# stepper_driver.net
KiCad netlist of a schematic drawn in Altium Designer
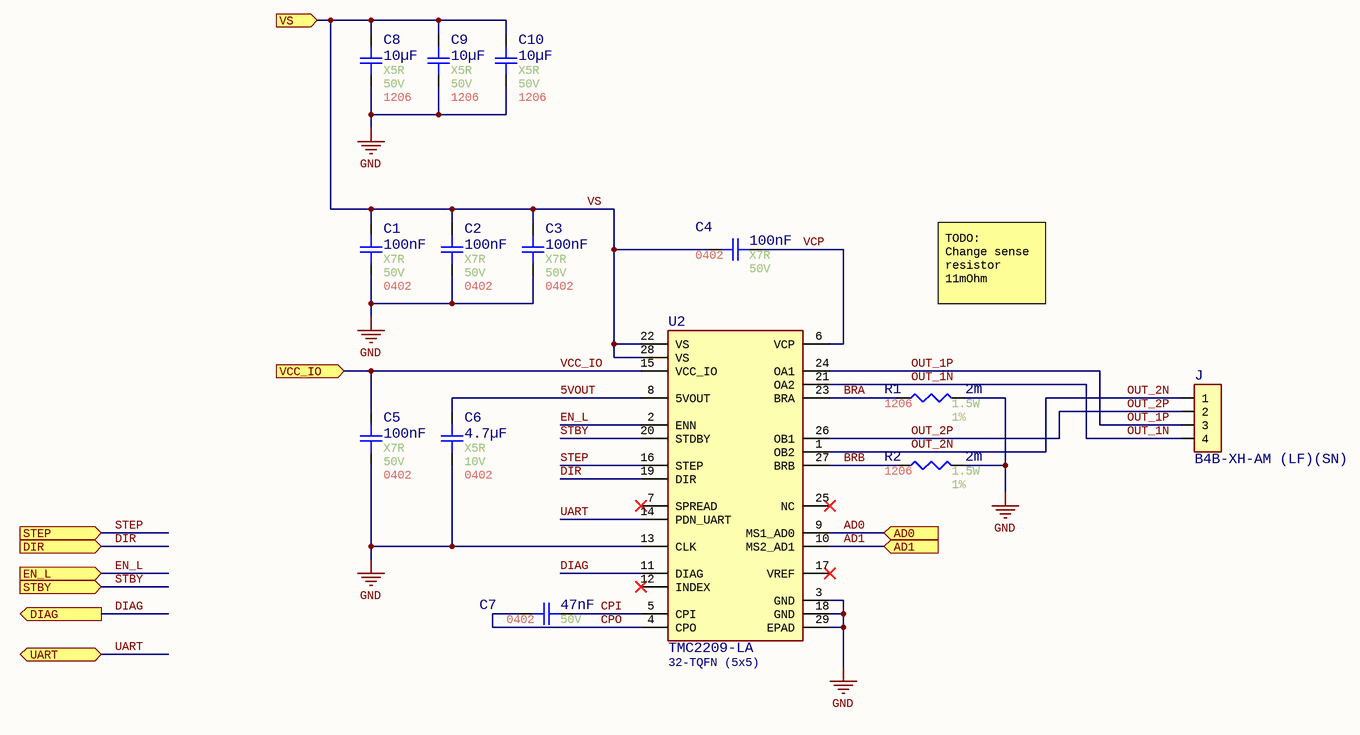
[diagram p0: stepper_driver.SchDoc]

(export (version "E")
  (design (tool "Eeschema 10.0.6"))
  (components
    (comp (ref "C1")
      (value "100nF")
      (footprint "Generic 0402 capacitor")
      (fields
        (field (name "TEMPERATURE COEFFICIENT") "X7R")
        (field (name "VOLTAGE RATING") "50V")
        (field (name "CASE/PACKAGE") "0402")
        (field (name "TOLERANCE") "10%")
        (field (name "Comment") "GRT155R71H104KE01D")
      )
      (libsource (lib "Raise Robotics") (part "Unpolarized Capacitor"))
    )
    (comp (ref "C2")
      (value "100nF")
      (footprint "Generic 0402 capacitor")
      (fields
        (field (name "TEMPERATURE COEFFICIENT") "X7R")
        (field (name "VOLTAGE RATING") "50V")
        (field (name "CASE/PACKAGE") "0402")
        (field (name "TOLERANCE") "10%")
        (field (name "Comment") "GRT155R71H104KE01D")
      )
      (libsource (lib "Raise Robotics") (part "Unpolarized Capacitor"))
    )
    (comp (ref "C3")
      (value "100nF")
      (footprint "Generic 0402 capacitor")
      (fields
        (field (name "TEMPERATURE COEFFICIENT") "X7R")
        (field (name "VOLTAGE RATING") "50V")
        (field (name "CASE/PACKAGE") "0402")
        (field (name "TOLERANCE") "10%")
        (field (name "Comment") "GRT155R71H104KE01D")
      )
      (libsource (lib "Raise Robotics") (part "Unpolarized Capacitor"))
    )
    (comp (ref "C4")
      (value "100nF")
      (footprint "Generic 0402 capacitor")
      (fields
        (field (name "TEMPERATURE COEFFICIENT") "X7R")
        (field (name "VOLTAGE RATING") "50V")
        (field (name "CASE/PACKAGE") "0402")
        (field (name "TOLERANCE") "10%")
        (field (name "Comment") "GRT155R71H104KE01D")
      )
      (libsource (lib "Raise Robotics") (part "Unpolarized Capacitor"))
    )
    (comp (ref "C5")
      (value "100nF")
      (footprint "Generic 0402 capacitor")
      (fields
        (field (name "TEMPERATURE COEFFICIENT") "X7R")
        (field (name "VOLTAGE RATING") "50V")
        (field (name "CASE/PACKAGE") "0402")
        (field (name "TOLERANCE") "10%")
        (field (name "Comment") "GRT155R71H104KE01D")
      )
      (libsource (lib "Raise Robotics") (part "Unpolarized Capacitor"))
    )
    (comp (ref "C6")
      (value "4.7µF")
      (footprint "Generic 0402 capacitor")
      (fields
        (field (name "TEMPERATURE COEFFICIENT") "X5R")
        (field (name "VOLTAGE RATING") "10V")
        (field (name "CASE/PACKAGE") "0402")
        (field (name "TOLERANCE") "0%")
        (field (name "Comment") "GRT155R61A475ME13D")
      )
      (libsource (lib "Raise Robotics") (part "Unpolarized Capacitor"))
    )
    (comp (ref "C7")
      (value "47nF")
      (footprint "Generic 0402 capacitor")
      (description "50V 47nF X7R ±10% 0402 Multilayer Ceramic Capacitors MLCC - SMD/SMT ROHS")
      (fields
        (field (name "VOLTAGE RATING") "50V")
        (field (name "CASE/PACKAGE") "0402")
        (field (name "TOLERANCE") "10%")
        (field (name "Comment") "GRM155R71H473KE14D")
      )
      (libsource (lib "Raise Robotics") (part "Unpolarized Capacitor"))
    )
    (comp (ref "C8")
      (value "10µF")
      (footprint "Generic 1206 Capacitor")
      (fields
        (field (name "TEMPERATURE COEFFICIENT") "X5R")
        (field (name "VOLTAGE RATING") "50V")
        (field (name "CASE/PACKAGE") "1206")
        (field (name "TOLERANCE") "20%")
        (field (name "Comment") "CL31A106MBHNNNE")
      )
      (libsource (lib "Raise Robotics") (part "Unpolarized Capacitor"))
    )
    (comp (ref "C9")
      (value "10µF")
      (footprint "Generic 1206 Capacitor")
      (fields
        (field (name "TEMPERATURE COEFFICIENT") "X5R")
        (field (name "VOLTAGE RATING") "50V")
        (field (name "CASE/PACKAGE") "1206")
        (field (name "TOLERANCE") "20%")
        (field (name "Comment") "CL31A106MBHNNNE")
      )
      (libsource (lib "Raise Robotics") (part "Unpolarized Capacitor"))
    )
    (comp (ref "C10")
      (value "10µF")
      (footprint "Generic 1206 Capacitor")
      (fields
        (field (name "TEMPERATURE COEFFICIENT") "X5R")
        (field (name "VOLTAGE RATING") "50V")
        (field (name "CASE/PACKAGE") "1206")
        (field (name "TOLERANCE") "20%")
        (field (name "Comment") "CL31A106MBHNNNE")
      )
      (libsource (lib "Raise Robotics") (part "Unpolarized Capacitor"))
    )
    (comp (ref "J")
      (value "B4B-XH-AM (LF)(SN)")
      (footprint "FP-B4B-XH-AM_LF_SN-MFG")
      (description "Header, Xh, Top, 4Way, 2.5Mm, Boss;")
      (fields (field (name "MANUFACTURER") "JST"))
      (libsource (lib "Raise Robotics") (part "4 pin generic conn"))
    )
    (comp (ref "R1")
      (value "2m")
      (footprint "Generic 1206 resistor")
      (description "Res 0.002 Ohm 1% 1.5W 1206")
      (fields
        (field (name "POWER") "1.5W")
        (field (name "TOLERANCE") "1%")
        (field (name "CASE/PACKAGE") "1206")
        (field (name "MANUFACTURER PART NUMBER") "Blank")
        (field (name "Comment") "PA1206FRM670R002L")
      )
      (libsource (lib "Raise Robotics") (part "Resistor"))
    )
    (comp (ref "R2")
      (value "2m")
      (footprint "Generic 1206 resistor")
      (description "Res 0.002 Ohm 1% 1.5W 1206")
      (fields
        (field (name "POWER") "1.5W")
        (field (name "TOLERANCE") "1%")
        (field (name "CASE/PACKAGE") "1206")
        (field (name "MANUFACTURER PART NUMBER") "Blank")
        (field (name "Comment") "PA1206FRM670R002L")
      )
      (libsource (lib "Raise Robotics") (part "Resistor"))
    )
    (comp (ref "U2")
      (value "TMC2209-LA")
      (footprint "QFN-28_5x5x0.9mm_P0.5mm")
      (description "Step/Direction StealthChop Stepper Motor Driver Two-Phase 4.75V to 29V 28-Pin QFN Tray")
      (fields (field (name "MPN") "TMC5240ATJ+T") (field (name "CASE/PACKAGE") "32-TQFN (5x5)"))
      (libsource (lib "Raise Robotics") (part "TMC2209"))
    )
  )
  (nets
    (net (code "1") (name "/5VOUT") (class "Default")
      (node (ref "C6") (pin "2") (pinfunction "2_2") (pintype "passive"))
      (node (ref "U2") (pin "8") (pinfunction "5VOUT_8") (pintype "passive"))
    )
    (net (code "2") (name "/AD0") (class "Default")
      (node (ref "U2") (pin "9") (pinfunction "MS1_AD0_9") (pintype "passive"))
    )
    (net (code "3") (name "/AD1") (class "Default")
      (node (ref "U2") (pin "10") (pinfunction "MS2_AD1_10") (pintype "passive"))
    )
    (net (code "4") (name "/BRA") (class "Default")
      (node (ref "R1") (pin "1") (pinfunction "1_1") (pintype "passive"))
      (node (ref "U2") (pin "23") (pinfunction "BRA_23") (pintype "passive"))
    )
    (net (code "5") (name "/BRB") (class "Default")
      (node (ref "R2") (pin "1") (pinfunction "1_1") (pintype "passive"))
      (node (ref "U2") (pin "27") (pinfunction "BRB_27") (pintype "passive"))
    )
    (net (code "6") (name "/CPI") (class "Default")
      (node (ref "C7") (pin "1") (pinfunction "1_1") (pintype "passive"))
      (node (ref "U2") (pin "5") (pinfunction "CPI_5") (pintype "passive"))
    )
    (net (code "7") (name "/CPO") (class "Default")
      (node (ref "C7") (pin "2") (pinfunction "2_2") (pintype "passive"))
      (node (ref "U2") (pin "4") (pinfunction "CPO_4") (pintype "passive"))
    )
    (net (code "8") (name "/DIAG") (class "Default")
      (node (ref "U2") (pin "11") (pinfunction "DIAG_11") (pintype "passive"))
    )
    (net (code "9") (name "/DIR") (class "Default")
      (node (ref "U2") (pin "19") (pinfunction "DIR_19") (pintype "passive"))
    )
    (net (code "10") (name "/EN_L") (class "Default")
      (node (ref "U2") (pin "2") (pinfunction "ENN_2") (pintype "passive"))
    )
    (net (code "11") (name "/OUT_1N") (class "Default")
      (node (ref "J") (pin "4") (pinfunction "4_4") (pintype "passive"))
      (node (ref "U2") (pin "21") (pinfunction "OA2_21") (pintype "passive"))
    )
    (net (code "12") (name "/OUT_1P") (class "Default")
      (node (ref "J") (pin "3") (pinfunction "3_3") (pintype "passive"))
      (node (ref "U2") (pin "24") (pinfunction "OA1_24") (pintype "passive"))
    )
    (net (code "13") (name "/OUT_2N") (class "Default")
      (node (ref "J") (pin "1") (pinfunction "1_1") (pintype "passive"))
      (node (ref "U2") (pin "1") (pinfunction "OB2_1") (pintype "passive"))
    )
    (net (code "14") (name "/OUT_2P") (class "Default")
      (node (ref "J") (pin "2") (pinfunction "2_2") (pintype "passive"))
      (node (ref "U2") (pin "26") (pinfunction "OB1_26") (pintype "passive"))
    )
    (net (code "15") (name "/STBY") (class "Default")
      (node (ref "U2") (pin "20") (pinfunction "STDBY_20") (pintype "passive"))
    )
    (net (code "16") (name "/STEP") (class "Default")
      (node (ref "U2") (pin "16") (pinfunction "STEP_16") (pintype "passive"))
    )
    (net (code "17") (name "/UART") (class "Default")
      (node (ref "U2") (pin "14") (pinfunction "PDN_UART_14") (pintype "passive"))
    )
    (net (code "18") (name "/VCC_IO") (class "Default")
      (node (ref "C5") (pin "2") (pinfunction "2_2") (pintype "passive"))
      (node (ref "U2") (pin "15") (pinfunction "VCC_IO_15") (pintype "passive"))
    )
    (net (code "19") (name "/VCP") (class "Default")
      (node (ref "C4") (pin "1") (pinfunction "1_1") (pintype "passive"))
      (node (ref "U2") (pin "6") (pinfunction "VCP_6") (pintype "passive"))
    )
    (net (code "20") (name "/VS") (class "Default")
      (node (ref "C1") (pin "2") (pinfunction "2_2") (pintype "passive"))
      (node (ref "C10") (pin "2") (pinfunction "2_2") (pintype "passive"))
      (node (ref "C2") (pin "2") (pinfunction "2_2") (pintype "passive"))
      (node (ref "C3") (pin "2") (pinfunction "2_2") (pintype "passive"))
      (node (ref "C4") (pin "2") (pinfunction "2_2") (pintype "passive"))
      (node (ref "C8") (pin "2") (pinfunction "2_2") (pintype "passive"))
      (node (ref "C9") (pin "2") (pinfunction "2_2") (pintype "passive"))
      (node (ref "U2") (pin "22") (pinfunction "VS_22") (pintype "passive"))
      (node (ref "U2") (pin "28") (pinfunction "VS_28") (pintype "passive"))
    )
    (net (code "21") (name "GND") (class "Default")
      (node (ref "C1") (pin "1") (pinfunction "1_1") (pintype "passive"))
      (node (ref "C10") (pin "1") (pinfunction "1_1") (pintype "passive"))
      (node (ref "C2") (pin "1") (pinfunction "1_1") (pintype "passive"))
      (node (ref "C3") (pin "1") (pinfunction "1_1") (pintype "passive"))
      (node (ref "C5") (pin "1") (pinfunction "1_1") (pintype "passive"))
      (node (ref "C6") (pin "1") (pinfunction "1_1") (pintype "passive"))
      (node (ref "C8") (pin "1") (pinfunction "1_1") (pintype "passive"))
      (node (ref "C9") (pin "1") (pinfunction "1_1") (pintype "passive"))
      (node (ref "R1") (pin "2") (pinfunction "2_2") (pintype "passive"))
      (node (ref "R2") (pin "2") (pinfunction "2_2") (pintype "passive"))
      (node (ref "U2") (pin "13") (pinfunction "CLK_13") (pintype "passive"))
      (node (ref "U2") (pin "18") (pinfunction "GND_18") (pintype "passive"))
      (node (ref "U2") (pin "29") (pinfunction "EPAD_29") (pintype "passive"))
      (node (ref "U2") (pin "3") (pinfunction "GND_3") (pintype "passive"))
    )
    (net (code "22") (name "unconnected-(U2-INDEX-Pad12)") (class "Default")
      (node (ref "U2") (pin "12") (pinfunction "INDEX_12") (pintype "passive+no_connect"))
    )
    (net (code "23") (name "unconnected-(U2-NC-Pad25)") (class "Default")
      (node (ref "U2") (pin "25") (pinfunction "NC_25") (pintype "passive+no_connect"))
    )
    (net (code "24") (name "unconnected-(U2-SPREAD-Pad7)") (class "Default")
      (node (ref "U2") (pin "7") (pinfunction "SPREAD_7") (pintype "passive+no_connect"))
    )
    (net (code "25") (name "unconnected-(U2-VREF-Pad17)") (class "Default")
      (node (ref "U2") (pin "17") (pinfunction "VREF_17") (pintype "passive+no_connect"))
    )
  )
)
